# RFID.net
KiCad netlist of a schematic drawn in Altium Designer
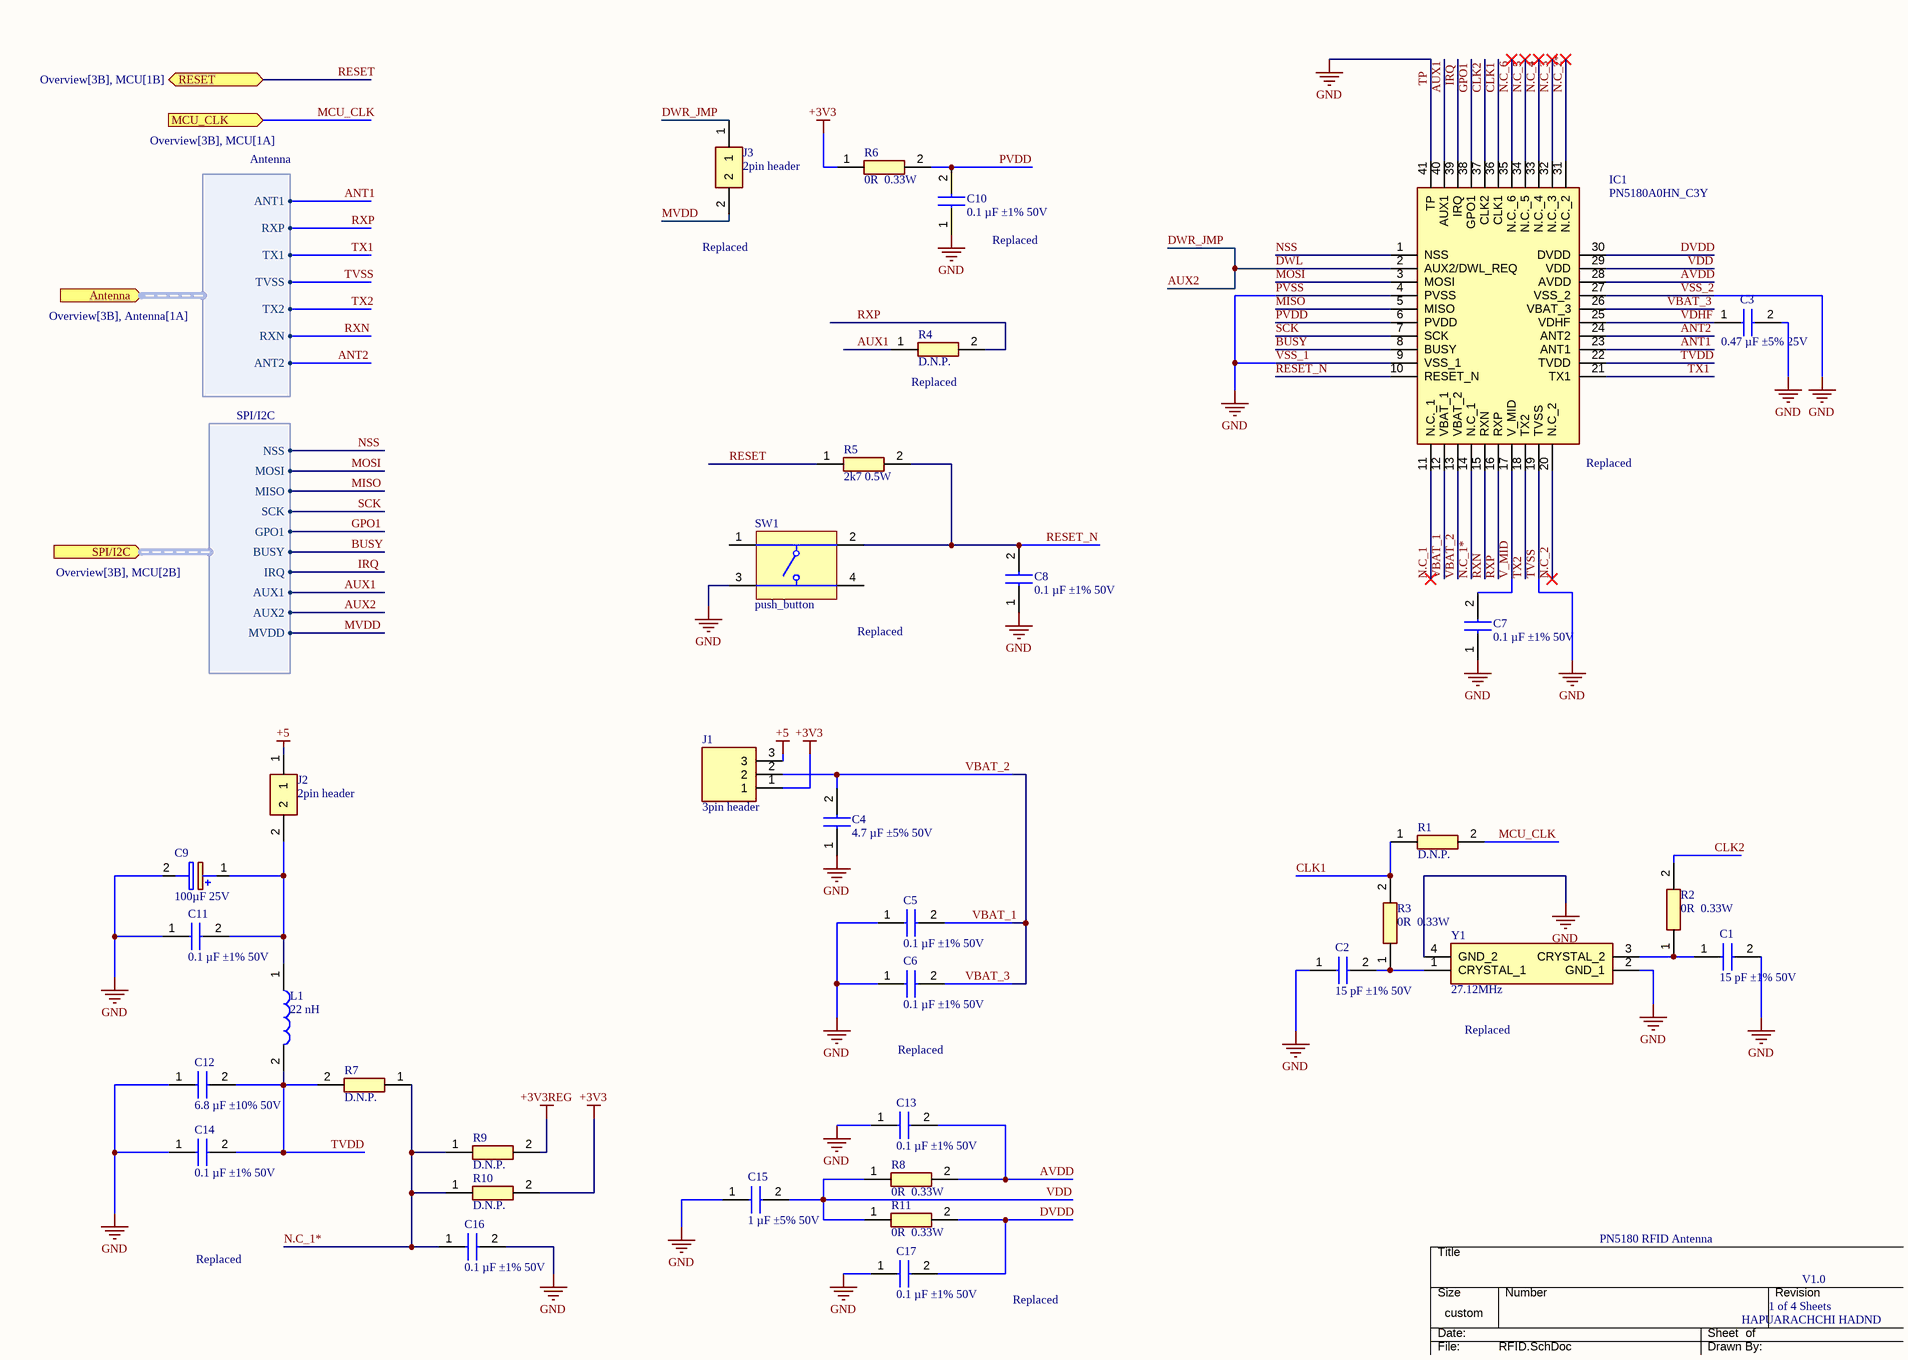
[diagram p0: RFID.SchDoc]

(export (version "E")
  (design (tool "Eeschema 10.0.6"))
  (components
    (comp (ref "C1")
      (value "15 pF ±1% 50V")
      (footprint "Antenna_Order:C0805")
      (description "15 pF ±1% 50V Ceramic Capacitor C0G, NP0 0805 (2012 Metric)")
      (fields
        (field (name "MANUFACTURER_PART_NUMBER") "C0805C150F5GACTU")
        (field (name "MOUSER PART NUMBER") "80-C0805C150F5GACTU")
      )
      (libsource (lib "Antenna_Order") (part "15pF"))
    )
    (comp (ref "C2")
      (value "15 pF ±1% 50V")
      (footprint "Antenna_Order:C0805")
      (description "15 pF ±1% 50V Ceramic Capacitor C0G, NP0 0805 (2012 Metric)")
      (fields
        (field (name "MANUFACTURER_PART_NUMBER") "C0805C150F5GACTU")
        (field (name "MOUSER PART NUMBER") "80-C0805C150F5GACTU")
      )
      (libsource (lib "Antenna_Order") (part "15pF"))
    )
    (comp (ref "C3")
      (value "0.47 µF ±5% 25V")
      (footprint "Antenna_Order:CAPC1608X90N")
      (description "0.47 µF ±5% 25V Ceramic Capacitor X7R 0603 (1608 Metric)")
      (fields
        (field (name "MANUFACTURER_PART_NUMBER") "06033C474JAT2A")
        (field (name "MOUSER PART NUMBER") "581-06033C474JAT2A")
      )
      (libsource (lib "Antenna_Order") (part "470nF"))
    )
    (comp (ref "C4")
      (value "4.7 µF ±5% 50V")
      (footprint "Antenna_Order:CAPC4532X279N")
      (description "4.7 µF ±5% 50V Ceramic Capacitor X7R 1812 (4532 Metric)")
      (fields
        (field (name "MANUFACTURER_PART_NUMBER") "18125C475JAT2A")
        (field (name "MOUSER PART NUMBER") "581-18125C475JAT2A")
      )
      (libsource (lib "Antenna_Order") (part "4.7uF"))
    )
    (comp (ref "C5")
      (value "0.1 µF ±1% 50V")
      (footprint "Antenna_Order:GRT31x")
      (description "0.1 µF ±1% 50V Ceramic Capacitor C0G, NP0 1206 (3216 Metric)")
      (fields
        (field (name "MANUFACTURER_PART_NUMBER") "GRT31C5C1H104FA02L")
        (field (name "MOUSER PART NUMBER") "81-GRT31C5C1H104FA2L")
      )
      (libsource (lib "Antenna_Order") (part "100nF"))
    )
    (comp (ref "C6")
      (value "0.1 µF ±1% 50V")
      (footprint "Antenna_Order:GRT31x")
      (description "0.1 µF ±1% 50V Ceramic Capacitor C0G, NP0 1206 (3216 Metric)")
      (fields
        (field (name "MANUFACTURER_PART_NUMBER") "GRT31C5C1H104FA02L")
        (field (name "MOUSER PART NUMBER") "81-GRT31C5C1H104FA2L")
      )
      (libsource (lib "Antenna_Order") (part "100nF"))
    )
    (comp (ref "C7")
      (value "0.1 µF ±1% 50V")
      (footprint "Antenna_Order:GRT31x")
      (description "0.1 µF ±1% 50V Ceramic Capacitor C0G, NP0 1206 (3216 Metric)")
      (fields
        (field (name "MANUFACTURER_PART_NUMBER") "GRT31C5C1H104FA02L")
        (field (name "MOUSER PART NUMBER") "81-GRT31C5C1H104FA2L")
      )
      (libsource (lib "Antenna_Order") (part "100nF"))
    )
    (comp (ref "C8")
      (value "0.1 µF ±1% 50V")
      (footprint "Antenna_Order:GRT31x")
      (description "0.1 µF ±1% 50V Ceramic Capacitor C0G, NP0 1206 (3216 Metric)")
      (fields
        (field (name "MANUFACTURER_PART_NUMBER") "GRT31C5C1H104FA02L")
        (field (name "MOUSER PART NUMBER") "81-GRT31C5C1H104FA2L")
      )
      (libsource (lib "Antenna_Order") (part "100nF"))
    )
    (comp (ref "C9")
      (value "100µF 25V")
      (footprint "Antenna_Order:EEHZA1E101XP")
      (description "Capacitor Polarised. Aluminum Organic Polymer Capacitors 100uF 25volt AEC-Q200")
      (fields
        (field (name "MANUFACTURER_PART_NUMBER") "EEH-ZA1E101XP")
        (field (name "MOUSER PART NUMBER") "667-EEH-ZA1E101XP")
      )
      (libsource (lib "Antenna_Order") (part "100µF"))
    )
    (comp (ref "C10")
      (value "0.1 µF ±1% 50V")
      (footprint "Antenna_Order:GRT31x")
      (description "0.1 µF ±1% 50V Ceramic Capacitor C0G, NP0 1206 (3216 Metric)")
      (fields
        (field (name "MANUFACTURER_PART_NUMBER") "GRT31C5C1H104FA02L")
        (field (name "MOUSER PART NUMBER") "81-GRT31C5C1H104FA2L")
      )
      (libsource (lib "Antenna_Order") (part "100nF"))
    )
    (comp (ref "C11")
      (value "0.1 µF ±1% 50V")
      (footprint "Antenna_Order:GRT31x")
      (description "0.1 µF ±1% 50V Ceramic Capacitor C0G, NP0 1206 (3216 Metric)")
      (fields
        (field (name "MANUFACTURER_PART_NUMBER") "GRT31C5C1H104FA02L")
        (field (name "MOUSER PART NUMBER") "81-GRT31C5C1H104FA2L")
      )
      (libsource (lib "Antenna_Order") (part "100nF"))
    )
    (comp (ref "C12")
      (value "6.8 µF ±10% 50V")
      (footprint "Antenna_Order:CAPC3216X180N")
      (description "6.8 µF ±10% 50V Ceramic Capacitor X5R 1206 (3216 Metric)")
      (fields
        (field (name "MANUFACTURER_PART_NUMBER") "C3216X5R1H685K160AB")
        (field (name "MOUSER PART NUMBER") "810-C3216X5R1H685K")
      )
      (libsource (lib "Antenna_Order") (part "6.8uF"))
    )
    (comp (ref "C13")
      (value "0.1 µF ±1% 50V")
      (footprint "Antenna_Order:GRT31x")
      (description "0.1 µF ±1% 50V Ceramic Capacitor C0G, NP0 1206 (3216 Metric)")
      (fields
        (field (name "MANUFACTURER_PART_NUMBER") "GRT31C5C1H104FA02L")
        (field (name "MOUSER PART NUMBER") "81-GRT31C5C1H104FA2L")
      )
      (libsource (lib "Antenna_Order") (part "100nF"))
    )
    (comp (ref "C14")
      (value "0.1 µF ±1% 50V")
      (footprint "Antenna_Order:GRT31x")
      (description "0.1 µF ±1% 50V Ceramic Capacitor C0G, NP0 1206 (3216 Metric)")
      (fields
        (field (name "MANUFACTURER_PART_NUMBER") "GRT31C5C1H104FA02L")
        (field (name "MOUSER PART NUMBER") "81-GRT31C5C1H104FA2L")
      )
      (libsource (lib "Antenna_Order") (part "100nF"))
    )
    (comp (ref "C15")
      (value "1 µF ±5% 50V")
      (footprint "Antenna_Order:RESC2012X140N")
      (description "1 µF ±5% 50V Ceramic Capacitor X7R 0805 (2012 Metric)")
      (fields
        (field (name "MANUFACTURER_PART_NUMBER") "08055C105JAT2A")
        (field (name "MOUSER PART NUMBER") "581-08055C105JAT2A")
      )
      (libsource (lib "Antenna_Order") (part "1uF"))
    )
    (comp (ref "C16")
      (value "0.1 µF ±1% 50V")
      (footprint "Antenna_Order:GRT31x")
      (description "0.1 µF ±1% 50V Ceramic Capacitor C0G, NP0 1206 (3216 Metric)")
      (fields
        (field (name "MANUFACTURER_PART_NUMBER") "GRT31C5C1H104FA02L")
        (field (name "MOUSER PART NUMBER") "81-GRT31C5C1H104FA2L")
      )
      (libsource (lib "Antenna_Order") (part "100nF"))
    )
    (comp (ref "C17")
      (value "0.1 µF ±1% 50V")
      (footprint "Antenna_Order:GRT31x")
      (description "0.1 µF ±1% 50V Ceramic Capacitor C0G, NP0 1206 (3216 Metric)")
      (fields
        (field (name "MANUFACTURER_PART_NUMBER") "GRT31C5C1H104FA02L")
        (field (name "MOUSER PART NUMBER") "81-GRT31C5C1H104FA2L")
      )
      (libsource (lib "Antenna_Order") (part "100nF"))
    )
    (comp (ref "IC1")
      (value "PN5180A0HN_C3Y")
      (footprint "Antenna_Order:QFN50P600X600X100-41N-D")
      (description "RF Front End High-Performance Multi-protocol Full NFC Forum-compliant Frontend PN5180A0HN/C3Y")
      (fields
        (field (name "MANUFACTURER_PART_NUMBER") "PN5180A0HN/C3Y")
        (field (name "MOUSER PART NUMBER") "771-PN5180A0HN/C3Y")
      )
      (libsource (lib "Antenna_Order") (part "PN5180A0HN_C3Y"))
    )
    (comp (ref "J1")
      (value "3pin header")
      (footprint "Antenna_Order:HDRV3W64P0X254_1X3_762X254X864P")
      (description "Connector Header Through Hole 3 position 0.100\" (2.54mm)")
      (fields
        (field (name "MANUFACTURER_PART_NUMBER") "M20-9990345")
        (field (name "MOUSER PART NUMBER") "855-M20-9990345")
      )
      (libsource (lib "Antenna_Order") (part "3pin header"))
    )
    (comp (ref "J2")
      (value "2pin header")
      (footprint "Antenna_Order:HDRV2W110P0X254_1X2_508X254X854P")
      (description "Connector Header Through Hole 2 position 0.100\" (2.54mm)")
      (fields
        (field (name "MANUFACTURER_PART_NUMBER") "61300211121")
        (field (name "MOUSER PART NUMBER") "710-61300211121")
      )
      (libsource (lib "Antenna_Order") (part "2pin header"))
    )
    (comp (ref "J3")
      (value "2pin header")
      (footprint "Antenna_Order:HDRV2W110P0X254_1X2_508X254X854P")
      (description "Connector Header Through Hole 2 position 0.100\" (2.54mm)")
      (fields
        (field (name "MANUFACTURER_PART_NUMBER") "61300211121")
        (field (name "MOUSER PART NUMBER") "710-61300211121")
      )
      (libsource (lib "Antenna_Order") (part "2pin header"))
    )
    (comp (ref "L1")
      (value "22 nH")
      (footprint "Antenna_Order:INDC2012X115N")
      (description "22 nH Unshielded Multilayer Inductor 300 mA 500mOhm Max 0805 (2012 Metric)")
      (fields
        (field (name "MANUFACTURER_PART_NUMBER") "AIMC-0805-22NJ-T")
        (field (name "MOUSER PART NUMBER") "815-AIMC-0805-22NJT")
      )
      (libsource (lib "Antenna_Order") (part "22nH"))
    )
    (comp (ref "R1")
      (value "D.N.P.")
      (footprint "Antenna_Order:RESC1608X50N_DNP")
      (description "Thick Film Resistors - SMD D11/CRCW0603 0R0 ET2 e3")
      (fields
        (field (name "MANUFACTURER_PART_NUMBER") "CRCW06030000Z0EI")
        (field (name "MOUSER PART NUMBER") "71-CRCW06030000Z0EI")
      )
      (libsource (lib "Antenna_Order") (part "DNP"))
    )
    (comp (ref "R2")
      (value "0R  0.33W")
      (footprint "Antenna_Order:RESC1608X50N_1")
      (description "Thick Film Resistors - SMD D11/CRCW0603 0R0 ET2 e3")
      (fields
        (field (name "MANUFACTURER_PART_NUMBER") "CRCW06030000Z0EI")
        (field (name "MOUSER PART NUMBER") "71-CRCW06030000Z0EI")
      )
      (libsource (lib "") (part "0R_1"))
    )
    (comp (ref "R3")
      (value "0R  0.33W")
      (footprint "Antenna_Order:RESC1608X50N_1")
      (description "Thick Film Resistors - SMD D11/CRCW0603 0R0 ET2 e3")
      (fields
        (field (name "MANUFACTURER_PART_NUMBER") "CRCW06030000Z0EI")
        (field (name "MOUSER PART NUMBER") "71-CRCW06030000Z0EI")
      )
      (libsource (lib "") (part "0R_1"))
    )
    (comp (ref "R4")
      (value "D.N.P.")
      (footprint "Antenna_Order:RESC1608X50N_DNP")
      (description "Thick Film Resistors - SMD D11/CRCW0603 0R0 ET2 e3")
      (fields
        (field (name "MANUFACTURER_PART_NUMBER") "CRCW06030000Z0EI")
        (field (name "MOUSER PART NUMBER") "71-CRCW06030000Z0EI")
      )
      (libsource (lib "Antenna_Order") (part "DNP"))
    )
    (comp (ref "R5")
      (value "2k7 0.5W")
      (footprint "Antenna_Order:RESC2012X60N")
      (fields
        (field (name "MANUFACTURER_PART_NUMBER") "CRCW08052K70FKEAHP")
        (field (name "MOUSER PART NUMBER") "71-CRCW08052K70FKEAH")
      )
      (libsource (lib "Antenna_Order") (part "2k7Ohm"))
    )
    (comp (ref "R6")
      (value "0R  0.33W")
      (footprint "Antenna_Order:RESC1608X50N_1")
      (description "Thick Film Resistors - SMD D11/CRCW0603 0R0 ET2 e3")
      (fields
        (field (name "MANUFACTURER_PART_NUMBER") "CRCW06030000Z0EI")
        (field (name "MOUSER PART NUMBER") "71-CRCW06030000Z0EI")
      )
      (libsource (lib "Antenna_Order") (part "0R"))
    )
    (comp (ref "R7")
      (value "D.N.P.")
      (footprint "Antenna_Order:RESC1608X50N_DNP")
      (description "Thick Film Resistors - SMD D11/CRCW0603 0R0 ET2 e3")
      (fields
        (field (name "MANUFACTURER_PART_NUMBER") "CRCW06030000Z0EI")
        (field (name "MOUSER PART NUMBER") "71-CRCW06030000Z0EI")
      )
      (libsource (lib "") (part "DNP_1"))
    )
    (comp (ref "R8")
      (value "0R  0.33W")
      (footprint "Antenna_Order:RESC1608X50N_1")
      (description "Thick Film Resistors - SMD D11/CRCW0603 0R0 ET2 e3")
      (fields
        (field (name "MANUFACTURER_PART_NUMBER") "CRCW06030000Z0EI")
        (field (name "MOUSER PART NUMBER") "71-CRCW06030000Z0EI")
      )
      (libsource (lib "Antenna_Order") (part "0R"))
    )
    (comp (ref "R9")
      (value "D.N.P.")
      (footprint "Antenna_Order:RESC1608X50N_DNP")
      (description "Thick Film Resistors - SMD D11/CRCW0603 0R0 ET2 e3")
      (fields
        (field (name "MANUFACTURER_PART_NUMBER") "CRCW06030000Z0EI")
        (field (name "MOUSER PART NUMBER") "71-CRCW06030000Z0EI")
      )
      (libsource (lib "Antenna_Order") (part "DNP"))
    )
    (comp (ref "R10")
      (value "D.N.P.")
      (footprint "Antenna_Order:RESC1608X50N_DNP")
      (description "Thick Film Resistors - SMD D11/CRCW0603 0R0 ET2 e3")
      (fields
        (field (name "MANUFACTURER_PART_NUMBER") "CRCW06030000Z0EI")
        (field (name "MOUSER PART NUMBER") "71-CRCW06030000Z0EI")
      )
      (libsource (lib "Antenna_Order") (part "DNP"))
    )
    (comp (ref "R11")
      (value "0R  0.33W")
      (footprint "Antenna_Order:RESC1608X50N_1")
      (description "Thick Film Resistors - SMD D11/CRCW0603 0R0 ET2 e3")
      (fields
        (field (name "MANUFACTURER_PART_NUMBER") "CRCW06030000Z0EI")
        (field (name "MOUSER PART NUMBER") "71-CRCW06030000Z0EI")
      )
      (libsource (lib "Antenna_Order") (part "0R"))
    )
    (comp (ref "SW1")
      (value "push_button")
      (footprint "TECO-1825910-6_V")
      (description "Tact Switch, SPST-NO, 0.05 A, -35 to 85 degC, 4-Pin THD, RoHS, Bulk")
      (fields (field (name "PART NO") "1825910-6") (field (name "MANUFACTURER") "TE Connectivity"))
      (libsource (lib "Altium Content Vault") (part "SW-SPST-4_A"))
    )
    (comp (ref "Y1")
      (value "27.12MHz")
      (footprint "Antenna_Order:7M27120MEEQT")
      (description "27.12 MHz ±10ppm Crystal 10pF 50 Ohms 4-SMD, No Lead")
      (fields
        (field (name "MANUFACTURER_PART_NUMBER") "7M-27.120MEEQ-T")
        (field (name "MOUSER PART NUMBER") "717-7M-27.120MEEQ-T")
      )
      (libsource (lib "Antenna_Order") (part "27.12MHz"))
    )
  )
  (nets
    (net (code "3") (name "+3V3") (class "Default")
      (node (ref "J1") (pin "1") (pinfunction "1_1") (pintype "passive"))
      (node (ref "R10") (pin "2") (pinfunction "2_2") (pintype "passive"))
      (node (ref "R6") (pin "1") (pinfunction "1_1") (pintype "passive"))
    )
    (net (code "4") (name "+3V3REG") (class "Default")
      (node (ref "R9") (pin "2") (pinfunction "2_2") (pintype "passive"))
    )
    (net (code "5") (name "+5") (class "Default")
      (node (ref "J1") (pin "3") (pinfunction "3_3") (pintype "passive"))
      (node (ref "J2") (pin "1") (pinfunction "1_1") (pintype "passive"))
    )
    (net (code "6") (name "/ANT1") (class "Default")
      (node (ref "IC1") (pin "23") (pinfunction "ANT1_23") (pintype "passive"))
    )
    (net (code "7") (name "/ANT2") (class "Default")
      (node (ref "IC1") (pin "24") (pinfunction "ANT2_24") (pintype "passive"))
    )
    (net (code "8") (name "/AUX1") (class "Default")
      (node (ref "IC1") (pin "40") (pinfunction "AUX1_40") (pintype "passive"))
      (node (ref "R4") (pin "1") (pinfunction "1_1") (pintype "passive"))
    )
    (net (code "9") (name "/AUX2") (class "Default")
      (node (ref "IC1") (pin "2") (pinfunction "AUX2/DWL_REQ_2") (pintype "passive"))
      (node (ref "J3") (pin "1") (pinfunction "1_1") (pintype "passive"))
    )
    (net (code "10") (name "/AVDD") (class "Default")
      (node (ref "C13") (pin "2") (pinfunction "2_2") (pintype "passive"))
      (node (ref "IC1") (pin "28") (pinfunction "AVDD_28") (pintype "passive"))
      (node (ref "R8") (pin "2") (pinfunction "2_2") (pintype "passive"))
    )
    (net (code "11") (name "/BUSY") (class "Default")
      (node (ref "IC1") (pin "8") (pinfunction "BUSY_8") (pintype "passive"))
    )
    (net (code "12") (name "/CLK1") (class "Default")
      (node (ref "IC1") (pin "36") (pinfunction "CLK1_36") (pintype "passive"))
      (node (ref "R1") (pin "1") (pinfunction "1_1") (pintype "passive"))
      (node (ref "R3") (pin "2") (pinfunction "2_2") (pintype "passive"))
    )
    (net (code "13") (name "/CLK2") (class "Default")
      (node (ref "IC1") (pin "37") (pinfunction "CLK2_37") (pintype "passive"))
      (node (ref "R2") (pin "2") (pinfunction "2_2") (pintype "passive"))
    )
    (net (code "14") (name "/DVDD") (class "Default")
      (node (ref "C17") (pin "2") (pinfunction "2_2") (pintype "passive"))
      (node (ref "IC1") (pin "30") (pinfunction "DVDD_30") (pintype "passive"))
      (node (ref "R11") (pin "2") (pinfunction "2_2") (pintype "passive"))
    )
    (net (code "15") (name "/GPO1") (class "Default")
      (node (ref "IC1") (pin "38") (pinfunction "GPO1_38") (pintype "passive"))
    )
    (net (code "16") (name "/IRQ") (class "Default")
      (node (ref "IC1") (pin "39") (pinfunction "IRQ_39") (pintype "passive"))
    )
    (net (code "17") (name "/MCU_CLK") (class "Default")
      (node (ref "R1") (pin "2") (pinfunction "2_2") (pintype "passive"))
    )
    (net (code "18") (name "/MISO") (class "Default")
      (node (ref "IC1") (pin "5") (pinfunction "MISO_5") (pintype "passive"))
    )
    (net (code "19") (name "/MOSI") (class "Default")
      (node (ref "IC1") (pin "3") (pinfunction "MOSI_3") (pintype "passive"))
    )
    (net (code "20") (name "/MVDD") (class "Default")
      (node (ref "J3") (pin "2") (pinfunction "2_2") (pintype "passive"))
    )
    (net (code "21") (name "/N.C_1") (class "Default")
      (node (ref "IC1") (pin "11") (pinfunction "N.C._1_11") (pintype "passive+no_connect"))
    )
    (net (code "22") (name "/N.C_1*") (class "Default")
      (node (ref "C16") (pin "1") (pinfunction "1_1") (pintype "passive"))
      (node (ref "IC1") (pin "14") (pinfunction "N.C_1_14") (pintype "passive"))
      (node (ref "R10") (pin "1") (pinfunction "1_1") (pintype "passive"))
      (node (ref "R7") (pin "1") (pinfunction "1_1") (pintype "passive"))
      (node (ref "R9") (pin "1") (pinfunction "1_1") (pintype "passive"))
    )
    (net (code "23") (name "/N.C_2") (class "Default")
      (node (ref "IC1") (pin "20") (pinfunction "N.C_2_20") (pintype "passive+no_connect"))
    )
    (net (code "24") (name "/N.C_2*") (class "Default")
      (node (ref "IC1") (pin "31") (pinfunction "N.C._2_31") (pintype "passive+no_connect"))
    )
    (net (code "25") (name "/N.C_3") (class "Default")
      (node (ref "IC1") (pin "32") (pinfunction "N.C._3_32") (pintype "passive+no_connect"))
    )
    (net (code "26") (name "/N.C_4") (class "Default")
      (node (ref "IC1") (pin "33") (pinfunction "N.C._4_33") (pintype "passive+no_connect"))
    )
    (net (code "27") (name "/N.C_5") (class "Default")
      (node (ref "IC1") (pin "34") (pinfunction "N.C._5_34") (pintype "passive+no_connect"))
    )
    (net (code "28") (name "/N.C_6") (class "Default")
      (node (ref "IC1") (pin "35") (pinfunction "N.C._6_35") (pintype "passive+no_connect"))
    )
    (net (code "29") (name "/NSS") (class "Default")
      (node (ref "IC1") (pin "1") (pinfunction "NSS_1") (pintype "passive"))
    )
    (net (code "30") (name "/PVDD") (class "Default")
      (node (ref "C10") (pin "2") (pinfunction "2_2") (pintype "passive"))
      (node (ref "IC1") (pin "6") (pinfunction "PVDD_6") (pintype "passive"))
      (node (ref "R6") (pin "2") (pinfunction "2_2") (pintype "passive"))
    )
    (net (code "31") (name "/RESET") (class "Default")
      (node (ref "R5") (pin "1") (pinfunction "1_1") (pintype "passive"))
    )
    (net (code "32") (name "/RESET_N") (class "Default")
      (node (ref "C8") (pin "2") (pinfunction "2_2") (pintype "passive"))
      (node (ref "IC1") (pin "10") (pinfunction "RESET_N_10") (pintype "passive"))
      (node (ref "R5") (pin "2") (pinfunction "2_2") (pintype "passive"))
      (node (ref "SW1") (pin "2") (pinfunction "2_2") (pintype "passive"))
    )
    (net (code "33") (name "/RXN") (class "Default")
      (node (ref "IC1") (pin "15") (pinfunction "RXN_15") (pintype "passive"))
    )
    (net (code "34") (name "/RXP") (class "Default")
      (node (ref "IC1") (pin "16") (pinfunction "RXP_16") (pintype "passive"))
      (node (ref "R4") (pin "2") (pinfunction "2_2") (pintype "passive"))
    )
    (net (code "35") (name "/SCK") (class "Default")
      (node (ref "IC1") (pin "7") (pinfunction "SCK_7") (pintype "passive"))
    )
    (net (code "36") (name "/TVDD") (class "Default")
      (node (ref "C12") (pin "2") (pinfunction "2_2") (pintype "passive"))
      (node (ref "C14") (pin "2") (pinfunction "2_2") (pintype "passive"))
      (node (ref "IC1") (pin "22") (pinfunction "TVDD_22") (pintype "passive"))
      (node (ref "L1") (pin "2") (pinfunction "2_2") (pintype "passive"))
      (node (ref "R7") (pin "2") (pinfunction "2_2") (pintype "passive"))
    )
    (net (code "37") (name "/TX1") (class "Default")
      (node (ref "IC1") (pin "21") (pinfunction "TX1_21") (pintype "passive"))
    )
    (net (code "38") (name "/TX2") (class "Default")
      (node (ref "IC1") (pin "18") (pinfunction "TX2_18") (pintype "passive"))
    )
    (net (code "39") (name "/VBAT_1") (class "Default")
      (node (ref "C4") (pin "2") (pinfunction "2_2") (pintype "passive"))
      (node (ref "C5") (pin "2") (pinfunction "2_2") (pintype "passive"))
      (node (ref "C6") (pin "2") (pinfunction "2_2") (pintype "passive"))
      (node (ref "IC1") (pin "12") (pinfunction "VBAT_1_12") (pintype "passive"))
      (node (ref "IC1") (pin "13") (pinfunction "VBAT_2_13") (pintype "passive"))
      (node (ref "IC1") (pin "26") (pinfunction "VBAT_3_26") (pintype "passive"))
      (node (ref "J1") (pin "2") (pinfunction "2_2") (pintype "passive"))
    )
    (net (code "40") (name "/VDD") (class "Default")
      (node (ref "C15") (pin "2") (pinfunction "2_2") (pintype "passive"))
      (node (ref "IC1") (pin "29") (pinfunction "VDD_29") (pintype "passive"))
      (node (ref "R11") (pin "1") (pinfunction "1_1") (pintype "passive"))
      (node (ref "R8") (pin "1") (pinfunction "1_1") (pintype "passive"))
    )
    (net (code "41") (name "/VDHF") (class "Default")
      (node (ref "C3") (pin "1") (pinfunction "1_1") (pintype "passive"))
      (node (ref "IC1") (pin "25") (pinfunction "VDHF_25") (pintype "passive"))
    )
    (net (code "42") (name "/V_MID") (class "Default")
      (node (ref "C7") (pin "2") (pinfunction "2_2") (pintype "passive"))
      (node (ref "IC1") (pin "17") (pinfunction "V_MID_17") (pintype "passive"))
    )
    (net (code "45") (name "GND") (class "Default")
      (node (ref "C1") (pin "2") (pinfunction "2_2") (pintype "passive"))
      (node (ref "C10") (pin "1") (pinfunction "1_1") (pintype "passive"))
      (node (ref "C11") (pin "1") (pinfunction "1_1") (pintype "passive"))
      (node (ref "C12") (pin "1") (pinfunction "1_1") (pintype "passive"))
      (node (ref "C13") (pin "1") (pinfunction "1_1") (pintype "passive"))
      (node (ref "C14") (pin "1") (pinfunction "1_1") (pintype "passive"))
      (node (ref "C15") (pin "1") (pinfunction "1_1") (pintype "passive"))
      (node (ref "C16") (pin "2") (pinfunction "2_2") (pintype "passive"))
      (node (ref "C17") (pin "1") (pinfunction "1_1") (pintype "passive"))
      (node (ref "C2") (pin "1") (pinfunction "1_1") (pintype "passive"))
      (node (ref "C3") (pin "2") (pinfunction "2_2") (pintype "passive"))
      (node (ref "C4") (pin "1") (pinfunction "1_1") (pintype "passive"))
      (node (ref "C5") (pin "1") (pinfunction "1_1") (pintype "passive"))
      (node (ref "C6") (pin "1") (pinfunction "1_1") (pintype "passive"))
      (node (ref "C7") (pin "1") (pinfunction "1_1") (pintype "passive"))
      (node (ref "C8") (pin "1") (pinfunction "1_1") (pintype "passive"))
      (node (ref "C9") (pin "2") (pinfunction "-_2") (pintype "passive"))
      (node (ref "IC1") (pin "19") (pinfunction "TVSS_19") (pintype "passive"))
      (node (ref "IC1") (pin "27") (pinfunction "VSS_2_27") (pintype "passive"))
      (node (ref "IC1") (pin "4") (pinfunction "PVSS_4") (pintype "passive"))
      (node (ref "IC1") (pin "41") (pinfunction "TP_41") (pintype "passive"))
      (node (ref "IC1") (pin "9") (pinfunction "VSS_1_9") (pintype "passive"))
      (node (ref "SW1") (pin "3") (pinfunction "3_3") (pintype "passive"))
      (node (ref "Y1") (pin "2") (pinfunction "GND_1_2") (pintype "passive"))
      (node (ref "Y1") (pin "4") (pinfunction "GND_2_4") (pintype "passive"))
    )
    (net (code "46") (name "Net-(C9-+)") (class "Default")
      (node (ref "C11") (pin "2") (pinfunction "2_2") (pintype "passive"))
      (node (ref "C9") (pin "1") (pinfunction "+_1") (pintype "passive"))
      (node (ref "J2") (pin "2") (pinfunction "2_2") (pintype "passive"))
      (node (ref "L1") (pin "1") (pinfunction "1_1") (pintype "passive"))
    )
    (net (code "47") (name "Net-(Y1-CRYSTAL_1)") (class "Default")
      (node (ref "C2") (pin "2") (pinfunction "2_2") (pintype "passive"))
      (node (ref "R3") (pin "1") (pinfunction "1_1") (pintype "passive"))
      (node (ref "Y1") (pin "1") (pinfunction "CRYSTAL_1_1") (pintype "passive"))
    )
    (net (code "48") (name "Net-(Y1-CRYSTAL_2)") (class "Default")
      (node (ref "C1") (pin "1") (pinfunction "1_1") (pintype "passive"))
      (node (ref "R2") (pin "1") (pinfunction "1_1") (pintype "passive"))
      (node (ref "Y1") (pin "3") (pinfunction "CRYSTAL_2_3") (pintype "passive"))
    )
    (net (code "49") (name "unconnected-(SW1-Pad1)") (class "Default")
      (node (ref "SW1") (pin "1") (pinfunction "1_1") (pintype "passive"))
    )
    (net (code "50") (name "unconnected-(SW1-Pad4)") (class "Default")
      (node (ref "SW1") (pin "4") (pinfunction "4_4") (pintype "passive"))
    )
  )
)
